# Mechanical.net
KiCad netlist of a schematic drawn in Altium Designer
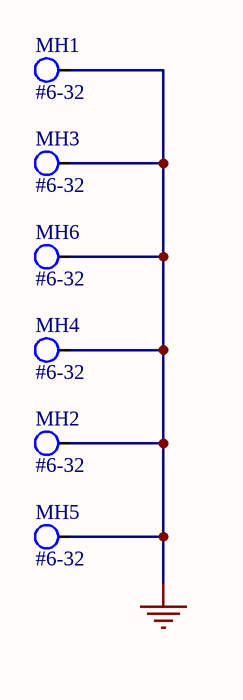
[diagram p0: Mechanical.SchDoc]

(export (version "E")
  (design (tool "Eeschema 10.0.6"))
  (components
    (comp (ref "MH1") (value "#6-32") (footprint "MH-6-32") (libsource (lib "PDU-UV17") (part "MH-6-32")))
    (comp (ref "MH2") (value "#6-32") (footprint "MH-6-32") (libsource (lib "PDU-UV17") (part "MH-6-32")))
    (comp (ref "MH3") (value "#6-32") (footprint "MH-6-32") (libsource (lib "PDU-UV17") (part "MH-6-32")))
    (comp (ref "MH4") (value "#6-32") (footprint "MH-6-32") (libsource (lib "PDU-UV17") (part "MH-6-32")))
    (comp (ref "MH5") (value "#6-32") (footprint "MH-6-32") (libsource (lib "PDU-UV17") (part "MH-6-32")))
    (comp (ref "MH6") (value "#6-32") (footprint "MH-6-32") (libsource (lib "PDU-UV17") (part "MH-6-32")))
  )
  (nets
    (net (code "1") (name "GND") (class "Default")
      (node (ref "MH1") (pin "1") (pinfunction "1_1") (pintype "passive"))
      (node (ref "MH2") (pin "1") (pinfunction "1_1") (pintype "passive"))
      (node (ref "MH3") (pin "1") (pinfunction "1_1") (pintype "passive"))
      (node (ref "MH4") (pin "1") (pinfunction "1_1") (pintype "passive"))
      (node (ref "MH5") (pin "1") (pinfunction "1_1") (pintype "passive"))
      (node (ref "MH6") (pin "1") (pinfunction "1_1") (pintype "passive"))
    )
  )
)
